# Pump_and_Power_IO.net
KiCad netlist of a schematic drawn in Altium Designer
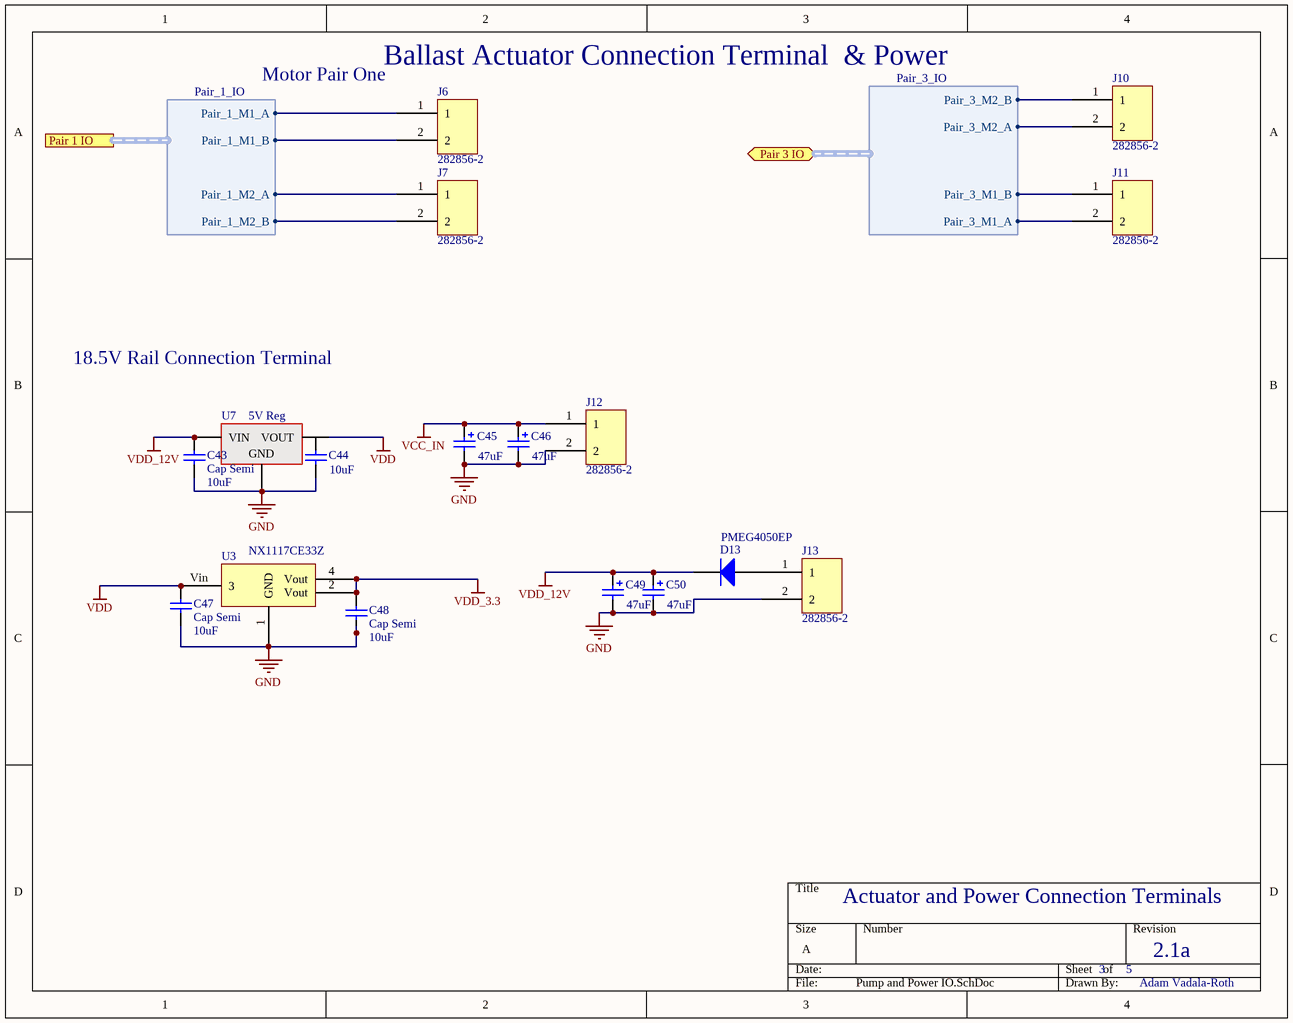
[diagram p0: Pump and Power IO.SchDoc]

(export (version "E")
  (design (tool "Eeschema 10.0.6"))
  (components
    (comp (ref "C43")
      (value "Cap Semi")
      (footprint "C1206")
      (description "Capacitor (Semiconductor SIM Model)")
      (fields (field (name "ALTIUM_VALUE") "10uF") (field (name "PUBLISHER") "Altium Limited"))
      (libsource (lib "Miscellaneous Devices") (part "Cap Semi"))
    )
    (comp (ref "C44")
      (value "10uF")
      (footprint "C1206")
      (description "Capacitor (Semiconductor SIM Model)")
      (fields (field (name "Comment") "Cap Semi") (field (name "PUBLISHER") "Altium Limited"))
      (libsource (lib "Miscellaneous Devices") (part "Cap Semi"))
    )
    (comp (ref "C45")
      (value "47uF")
      (footprint "CAPPR2-5x6.8")
      (description "Polarized Capacitor (Axial)")
      (fields (field (name "Comment") "Cap Pol2") (field (name "PUBLISHER") "Altium Limited"))
      (libsource (lib "Miscellaneous Devices") (part "Cap Pol2"))
    )
    (comp (ref "C46")
      (value "47uF")
      (footprint "CAPPR2-5x6.8")
      (description "Polarized Capacitor (Axial)")
      (fields (field (name "Comment") "Cap Pol2") (field (name "PUBLISHER") "Altium Limited"))
      (libsource (lib "Miscellaneous Devices") (part "Cap Pol2"))
    )
    (comp (ref "C47")
      (value "Cap Semi")
      (footprint "C1206")
      (description "Capacitor (Semiconductor SIM Model)")
      (fields (field (name "ALTIUM_VALUE") "10uF") (field (name "PUBLISHER") "Altium Limited"))
      (libsource (lib "Miscellaneous Devices") (part "Cap Semi"))
    )
    (comp (ref "C48")
      (value "Cap Semi")
      (footprint "C1206")
      (description "Capacitor (Semiconductor SIM Model)")
      (fields (field (name "ALTIUM_VALUE") "10uF") (field (name "PUBLISHER") "Altium Limited"))
      (libsource (lib "Miscellaneous Devices") (part "Cap Semi"))
    )
    (comp (ref "C49")
      (value "47uF")
      (footprint "CAPPR2-5x6.8")
      (description "Polarized Capacitor (Axial)")
      (fields (field (name "Comment") "Cap Pol2") (field (name "PUBLISHER") "Altium Limited"))
      (libsource (lib "Miscellaneous Devices") (part "Cap Pol2"))
    )
    (comp (ref "C50")
      (value "47uF")
      (footprint "CAPPR2-5x6.8")
      (description "Polarized Capacitor (Axial)")
      (fields (field (name "Comment") "Cap Pol2") (field (name "PUBLISHER") "Altium Limited"))
      (libsource (lib "Miscellaneous Devices") (part "Cap Pol2"))
    )
    (comp (ref "D13")
      (value "PMEG4050EP")
      (footprint "PMEG4050EP")
      (description "Default Diode")
      (fields (field (name "PUBLISHER") "Altium Limited"))
      (libsource (lib "Miscellaneous Devices") (part "Diode"))
    )
    (comp (ref "J6")
      (value "282856-2")
      (footprint "282856-2")
      (description "Two pole screw terminal")
      (libsource (lib "Thruster Shield Part Library") (part "282856-2"))
    )
    (comp (ref "J7")
      (value "282856-2")
      (footprint "282856-2")
      (description "Two pole screw terminal")
      (libsource (lib "Thruster Shield Part Library") (part "282856-2"))
    )
    (comp (ref "J10")
      (value "282856-2")
      (footprint "282856-2")
      (description "Two pole screw terminal")
      (libsource (lib "Thruster Shield Part Library") (part "282856-2"))
    )
    (comp (ref "J11")
      (value "282856-2")
      (footprint "282856-2")
      (description "Two pole screw terminal")
      (libsource (lib "Thruster Shield Part Library") (part "282856-2"))
    )
    (comp (ref "J12")
      (value "282856-2")
      (footprint "282856-2")
      (description "Two pole screw terminal")
      (libsource (lib "Thruster Shield Part Library") (part "282856-2"))
    )
    (comp (ref "J13")
      (value "282856-2")
      (footprint "282856-2")
      (description "Two pole screw terminal")
      (libsource (lib "Thruster Shield Part Library") (part "282856-2"))
    )
    (comp (ref "U3")
      (value "NX1117CE33Z")
      (footprint "NX1117CE33Z")
      (description "3.3v Linear Regulator")
      (libsource (lib "AHD Part Library") (part "NX1117CE33Z"))
    )
    (comp (ref "U7")
      (value "5V Reg")
      (footprint "DPAK-3")
      (description "Voltage regulator")
      (fields (field (name "PUBLISHER") "Altium Limited"))
      (libsource (lib "Rascal") (part "VOLT REG"))
    )
  )
  (nets
    (net (code "3") (name "/Pair_1_M1_A") (class "Default")
      (node (ref "J6") (pin "1") (pinfunction "1_1") (pintype "passive"))
    )
    (net (code "4") (name "/Pair_1_M1_B") (class "Default")
      (node (ref "J6") (pin "2") (pinfunction "2_2") (pintype "passive"))
    )
    (net (code "5") (name "/Pair_1_M2_A") (class "Default")
      (node (ref "J7") (pin "1") (pinfunction "1_1") (pintype "passive"))
    )
    (net (code "6") (name "/Pair_1_M2_B") (class "Default")
      (node (ref "J7") (pin "2") (pinfunction "2_2") (pintype "passive"))
    )
    (net (code "7") (name "/Pair_3_M1_A") (class "Default")
      (node (ref "J11") (pin "2") (pinfunction "2_2") (pintype "passive"))
    )
    (net (code "8") (name "/Pair_3_M1_B") (class "Default")
      (node (ref "J11") (pin "1") (pinfunction "1_1") (pintype "passive"))
    )
    (net (code "9") (name "/Pair_3_M2_A") (class "Default")
      (node (ref "J10") (pin "2") (pinfunction "2_2") (pintype "passive"))
    )
    (net (code "10") (name "/Pair_3_M2_B") (class "Default")
      (node (ref "J10") (pin "1") (pinfunction "1_1") (pintype "passive"))
    )
    (net (code "13") (name "GND") (class "Default")
      (node (ref "C43") (pin "1") (pinfunction "1_1") (pintype "passive"))
      (node (ref "C44") (pin "1") (pinfunction "1_1") (pintype "passive"))
      (node (ref "C45") (pin "2") (pinfunction "2_2") (pintype "passive"))
      (node (ref "C46") (pin "2") (pinfunction "2_2") (pintype "passive"))
      (node (ref "C47") (pin "1") (pinfunction "1_1") (pintype "passive"))
      (node (ref "C48") (pin "1") (pinfunction "1_1") (pintype "passive"))
      (node (ref "C49") (pin "2") (pinfunction "2_2") (pintype "passive"))
      (node (ref "C50") (pin "2") (pinfunction "2_2") (pintype "passive"))
      (node (ref "J12") (pin "2") (pinfunction "2_2") (pintype "passive"))
      (node (ref "J13") (pin "2") (pinfunction "2_2") (pintype "passive"))
      (node (ref "U3") (pin "1") (pinfunction "GND_1") (pintype "passive"))
      (node (ref "U7") (pin "2") (pinfunction "GND_2") (pintype "passive"))
    )
    (net (code "14") (name "Net-(D13-A)") (class "Default")
      (node (ref "D13") (pin "1") (pinfunction "A_1") (pintype "passive"))
      (node (ref "J13") (pin "1") (pinfunction "1_1") (pintype "passive"))
    )
    (net (code "15") (name "VCC_IN") (class "Default")
      (node (ref "C45") (pin "1") (pinfunction "1_1") (pintype "passive"))
      (node (ref "C46") (pin "1") (pinfunction "1_1") (pintype "passive"))
      (node (ref "J12") (pin "1") (pinfunction "1_1") (pintype "passive"))
    )
    (net (code "16") (name "VDD") (class "Default")
      (node (ref "C47") (pin "2") (pinfunction "2_2") (pintype "passive"))
      (node (ref "U3") (pin "Vin") (pinfunction "3_Vin") (pintype "passive"))
      (node (ref "U7") (pin "3") (pinfunction "VOUT_3") (pintype "passive"))
    )
    (net (code "17") (name "VDD_3.3") (class "Default")
      (node (ref "C48") (pin "2") (pinfunction "2_2") (pintype "passive"))
      (node (ref "U3") (pin "2") (pinfunction "Vout_2") (pintype "passive"))
      (node (ref "U3") (pin "4") (pinfunction "Vout_4") (pintype "passive"))
    )
    (net (code "18") (name "VDD_12V") (class "Default")
      (node (ref "C43") (pin "2") (pinfunction "2_2") (pintype "passive"))
      (node (ref "C49") (pin "1") (pinfunction "1_1") (pintype "passive"))
      (node (ref "C50") (pin "1") (pinfunction "1_1") (pintype "passive"))
      (node (ref "D13") (pin "2") (pinfunction "K_2") (pintype "passive"))
      (node (ref "U7") (pin "1") (pinfunction "VIN_1") (pintype "passive"))
    )
    (net (code "19") (name "unconnected-(C44-Pad2)") (class "Default")
      (node (ref "C44") (pin "2") (pinfunction "2_2") (pintype "passive"))
    )
  )
)
